# ECFFL2023-v2-schem.net
KiCad netlist of a schematic drawn in EasyEDA
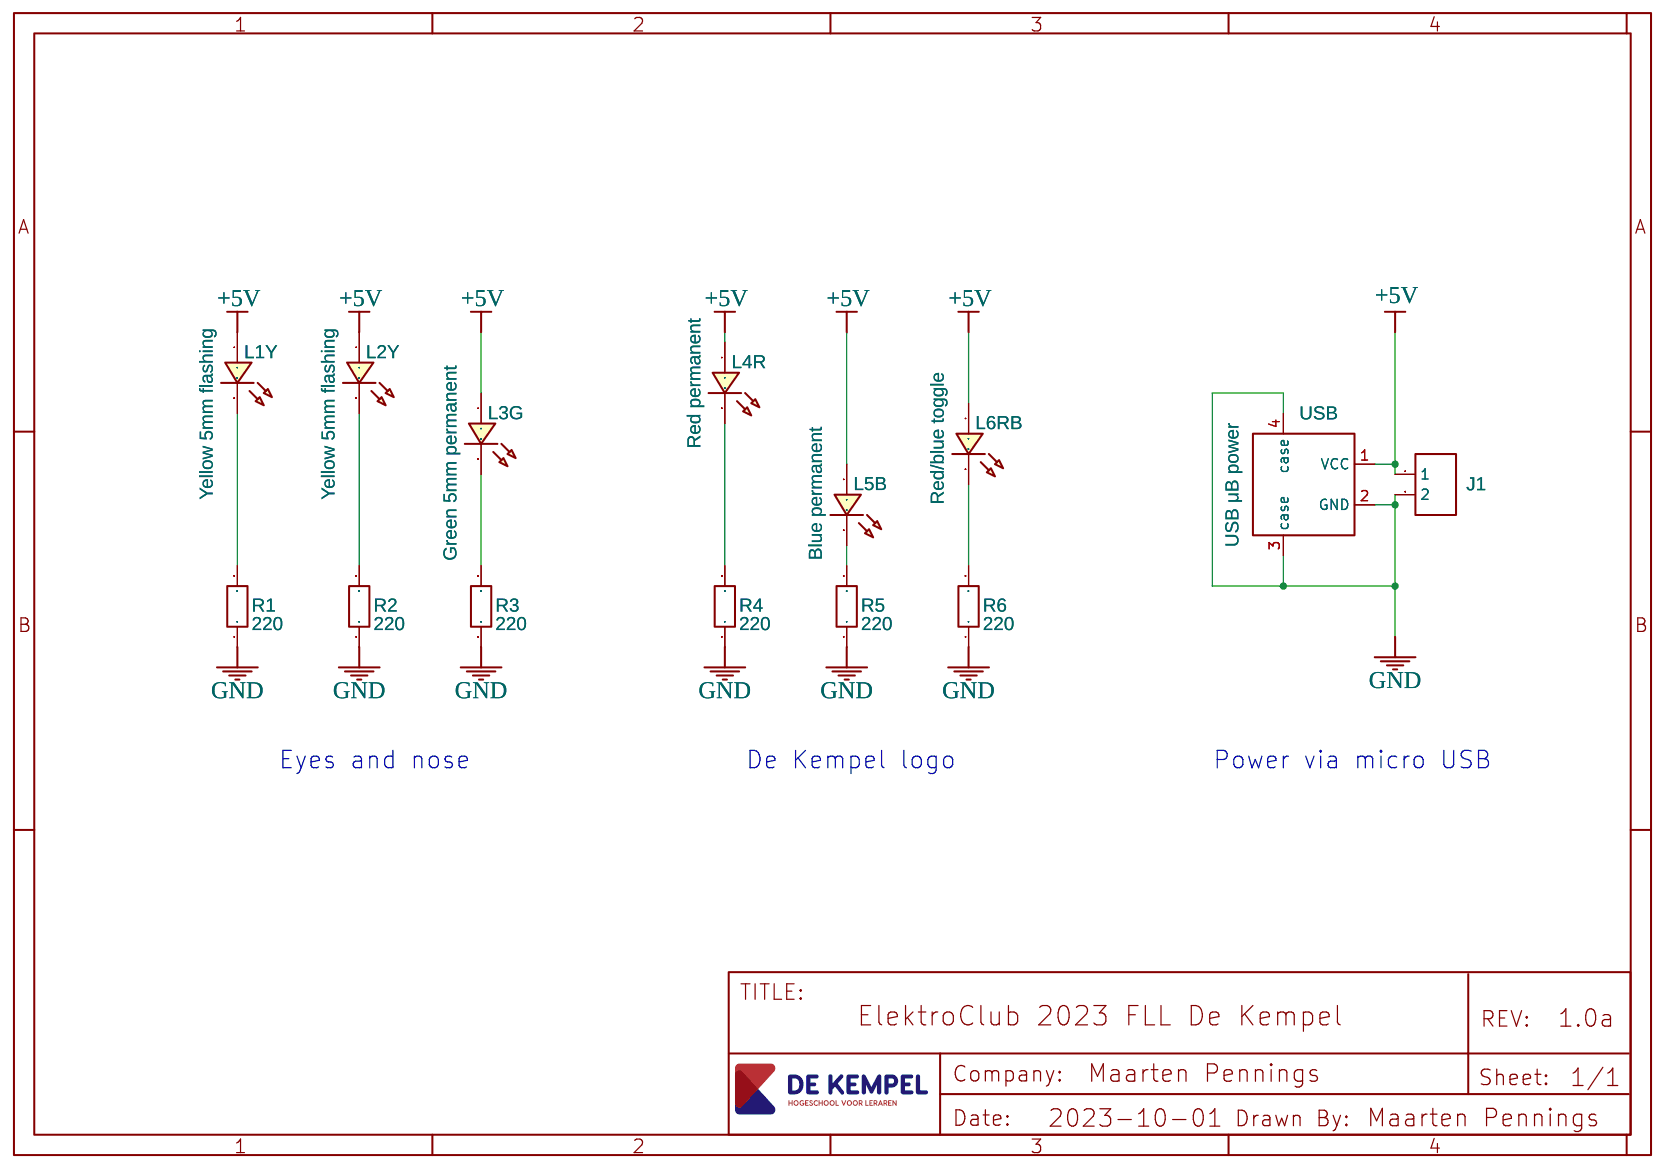
[diagram p0: schematic sheet]

(export (version "E")
  (design (tool "Eeschema 10.0.6"))
  (components
    (comp (ref "J1") (value "HDR-M-2.54_1x2") (libsource (lib "") (part "HDR-M-2.54_1x2")))
    (comp (ref "L1Y")
      (value "Yellow 5mm flashing")
      (fields
        (field (name "Manufacturer Part") "333-2SYGD/S530-E2")
        (field (name "Manufacturer") "EVERLIGHT(台湾亿光)")
      )
      (libsource (lib "") (part "LED-TH-5mm_G_2"))
    )
    (comp (ref "L2Y")
      (value "Yellow 5mm flashing")
      (fields
        (field (name "Manufacturer Part") "333-2SYGD/S530-E2")
        (field (name "Manufacturer") "EVERLIGHT(台湾亿光)")
      )
      (libsource (lib "") (part "LED-TH-5mm_G"))
    )
    (comp (ref "L3G")
      (value "Green 5mm permanent")
      (fields
        (field (name "Manufacturer Part") "333-2SYGD/S530-E2")
        (field (name "Manufacturer") "EVERLIGHT(台湾亿光)")
      )
      (libsource (lib "") (part "LED-TH-5mm_G_1"))
    )
    (comp (ref "L4R")
      (value "Red permanent")
      (fields
        (field (name "Manufacturer Part") "333-2SURD/S530-A3")
        (field (name "Manufacturer") "EVERLIGHT(台湾亿光)")
      )
      (libsource (lib "") (part "LED-TH-5mm_R"))
    )
    (comp (ref "L5B") (value "Blue permanent") (libsource (lib "") (part "LED-TH-5mm_B_1")))
    (comp (ref "L6RB") (value "Red/blue toggle") (libsource (lib "") (part "LED-TH-5mm_B")))
    (comp (ref "R1") (value "220") (libsource (lib "") (part "R_AXIAL-0.4_EU")))
    (comp (ref "R2") (value "220") (libsource (lib "") (part "R_AXIAL-0.4_EU")))
    (comp (ref "R3") (value "220") (libsource (lib "") (part "R_AXIAL-0.4_EU")))
    (comp (ref "R4") (value "220") (libsource (lib "") (part "R_AXIAL-0.4_EU")))
    (comp (ref "R5") (value "220") (libsource (lib "") (part "R_AXIAL-0.4_EU")))
    (comp (ref "R6") (value "220") (libsource (lib "") (part "R_AXIAL-0.4_EU")))
    (comp (ref "USB")
      (value "USB μB power")
      (fields (field (name "Manufacturer Part") "JK1-268") (field (name "Manufacturer") "HBXINTAO"))
      (libsource (lib "") (part "USB μB power"))
    )
  )
  (nets
    (net (code "1") (name "+5V") (class "Default")
      (node (ref "J1") (pin "1") (pinfunction "1_1") (pintype "unspecified"))
      (node (ref "L1Y") (pin "1") (pinfunction "1_1") (pintype "unspecified"))
      (node (ref "L2Y") (pin "1") (pinfunction "1_1") (pintype "unspecified"))
      (node (ref "L3G") (pin "1") (pinfunction "1_1") (pintype "unspecified"))
      (node (ref "L4R") (pin "1") (pinfunction "1_1") (pintype "unspecified"))
      (node (ref "L5B") (pin "1") (pinfunction "1_1") (pintype "unspecified"))
      (node (ref "L6RB") (pin "1") (pinfunction "1_1") (pintype "unspecified"))
      (node (ref "USB") (pin "1") (pinfunction "VCC_1") (pintype "unspecified"))
    )
    (net (code "2") (name "GND") (class "Default")
      (node (ref "J1") (pin "2") (pinfunction "2_2") (pintype "unspecified"))
      (node (ref "R1") (pin "1") (pinfunction "1_1") (pintype "unspecified"))
      (node (ref "R2") (pin "1") (pinfunction "1_1") (pintype "unspecified"))
      (node (ref "R3") (pin "1") (pinfunction "1_1") (pintype "unspecified"))
      (node (ref "R4") (pin "1") (pinfunction "1_1") (pintype "unspecified"))
      (node (ref "R5") (pin "1") (pinfunction "1_1") (pintype "unspecified"))
      (node (ref "R6") (pin "1") (pinfunction "1_1") (pintype "unspecified"))
      (node (ref "USB") (pin "2") (pinfunction "GND_2") (pintype "unspecified"))
      (node (ref "USB") (pin "3") (pinfunction "case_3") (pintype "unspecified"))
      (node (ref "USB") (pin "4") (pinfunction "case_4") (pintype "unspecified"))
    )
    (net (code "3") (name "Net-(L1Y-Pad2)") (class "Default")
      (node (ref "L1Y") (pin "2") (pinfunction "2_2") (pintype "unspecified"))
      (node (ref "R1") (pin "2") (pinfunction "2_2") (pintype "unspecified"))
    )
    (net (code "4") (name "Net-(L2Y-Pad2)") (class "Default")
      (node (ref "L2Y") (pin "2") (pinfunction "2_2") (pintype "unspecified"))
      (node (ref "R2") (pin "2") (pinfunction "2_2") (pintype "unspecified"))
    )
    (net (code "5") (name "Net-(L3G-Pad2)") (class "Default")
      (node (ref "L3G") (pin "2") (pinfunction "2_2") (pintype "unspecified"))
      (node (ref "R3") (pin "2") (pinfunction "2_2") (pintype "unspecified"))
    )
    (net (code "6") (name "Net-(L4R-Pad2)") (class "Default")
      (node (ref "L4R") (pin "2") (pinfunction "2_2") (pintype "unspecified"))
      (node (ref "R4") (pin "2") (pinfunction "2_2") (pintype "unspecified"))
    )
    (net (code "7") (name "Net-(L5B-Pad2)") (class "Default")
      (node (ref "L5B") (pin "2") (pinfunction "2_2") (pintype "unspecified"))
      (node (ref "R5") (pin "2") (pinfunction "2_2") (pintype "unspecified"))
    )
    (net (code "8") (name "Net-(L6RB-Pad2)") (class "Default")
      (node (ref "L6RB") (pin "2") (pinfunction "2_2") (pintype "unspecified"))
      (node (ref "R6") (pin "2") (pinfunction "2_2") (pintype "unspecified"))
    )
  )
)
